# Adafruit_MAX31855_v2.net
KiCad netlist of a schematic drawn in EAGLE
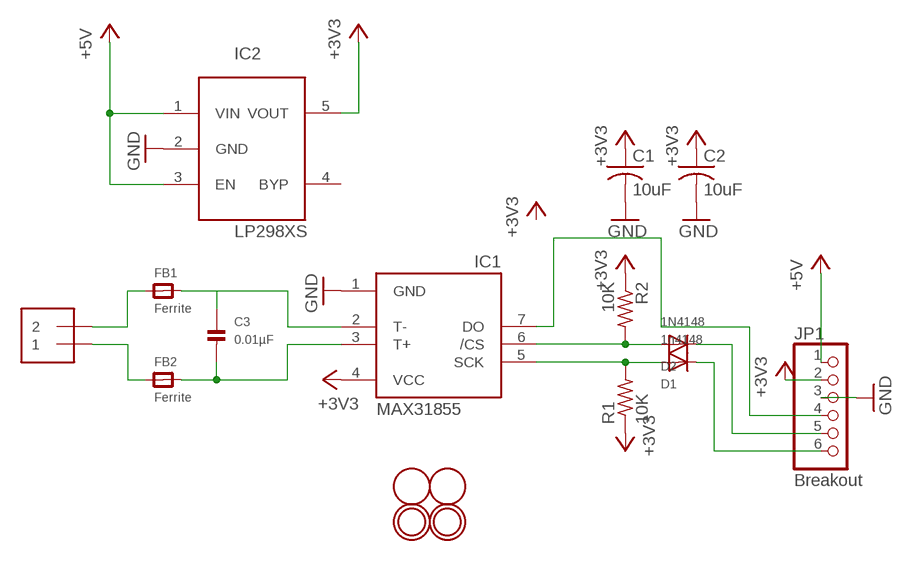
[diagram p0: schematic, sheet 1]

(export (version "E")
  (design (tool "Eeschema 10.0.6"))
  (components
    (comp (ref "C1")
      (value "10uF")
      (footprint "eagle-import:C0805K")
      (libsource (lib "eagle-import") (part "C-USC0805K"))
    )
    (comp (ref "C2")
      (value "10uF")
      (footprint "eagle-import:C0805K")
      (libsource (lib "eagle-import") (part "C-USC0805K"))
    )
    (comp (ref "C3")
      (value "0.01µF")
      (footprint "eagle-import:_0805")
      (libsource (lib "eagle-import") (part "CAP_CERAMIC_0805"))
    )
    (comp (ref "D1")
      (value "1n4148")
      (footprint "eagle-import:SOD-323F")
      (libsource (lib "eagle-import") (part "DIODESOD-323F"))
    )
    (comp (ref "D2")
      (value "1N4148")
      (footprint "eagle-import:SOD-323F")
      (libsource (lib "eagle-import") (part "DIODESOD-323F"))
    )
    (comp (ref "FB1")
      (value "Ferrite")
      (footprint "eagle-import:_0805")
      (libsource (lib "eagle-import") (part "FERRITE_0805"))
    )
    (comp (ref "FB2")
      (value "Ferrite")
      (footprint "eagle-import:_0805")
      (libsource (lib "eagle-import") (part "FERRITE_0805"))
    )
    (comp (ref "IC1")
      (value "MAX31855")
      (footprint "eagle-import:SO08")
      (libsource (lib "eagle-import") (part "MAX6675"))
    )
    (comp (ref "IC2")
      (value "LP298XS")
      (footprint "eagle-import:SOT23-5L")
      (libsource (lib "eagle-import") (part "LP298XS"))
    )
    (comp (ref "J1")
      (value "1X2-3.5MM")
      (footprint "eagle-import:1X2-3.5MM")
      (libsource (lib "eagle-import") (part "1X2-3.5MM"))
    )
    (comp (ref "JP1")
      (value "Breakout")
      (footprint "eagle-import:1X06_ROUND_76")
      (libsource (lib "eagle-import") (part "HEADER-1X676MIL"))
    )
    (comp (ref "R1")
      (value "10K")
      (footprint "eagle-import:R0805")
      (libsource (lib "eagle-import") (part "R-US_R0805"))
    )
    (comp (ref "R2")
      (value "10K")
      (footprint "eagle-import:R0805")
      (libsource (lib "eagle-import") (part "R-US_R0805"))
    )
    (comp (ref "U$1")
      (value "FIDUCIAL")
      (footprint "eagle-import:FIDUCIAL_1MM")
      (libsource (lib "eagle-import") (part "FIDUCIAL"))
    )
    (comp (ref "U$2")
      (value "FIDUCIAL")
      (footprint "eagle-import:FIDUCIAL_1MM")
      (libsource (lib "eagle-import") (part "FIDUCIAL"))
    )
    (comp (ref "U$4")
      (value "MOUNTINGHOLE2.0")
      (footprint "eagle-import:MOUNTINGHOLE_2.0_PLATED")
      (libsource (lib "eagle-import") (part "MOUNTINGHOLE2.0"))
    )
    (comp (ref "U$5")
      (value "MOUNTINGHOLE2.0")
      (footprint "eagle-import:MOUNTINGHOLE_2.0_PLATED")
      (libsource (lib "eagle-import") (part "MOUNTINGHOLE2.0"))
    )
  )
  (nets
    (net (code "1") (name "+3V3") (class "Default")
      (node (ref "C1") (pin "1") (pinfunction "1_1") (pintype "passive"))
      (node (ref "C2") (pin "1") (pinfunction "1_1") (pintype "passive"))
      (node (ref "IC1") (pin "4") (pinfunction "VCC_4") (pintype "power_in"))
      (node (ref "IC2") (pin "5") (pinfunction "VOUT_5") (pintype "bidirectional"))
      (node (ref "JP1") (pin "2") (pinfunction "2_2") (pintype "passive"))
      (node (ref "R1") (pin "1") (pinfunction "1_1") (pintype "passive"))
      (node (ref "R2") (pin "1") (pinfunction "1_1") (pintype "passive"))
    )
    (net (code "2") (name "+5V") (class "Default")
      (node (ref "IC2") (pin "1") (pinfunction "VIN_1") (pintype "bidirectional"))
      (node (ref "IC2") (pin "3") (pinfunction "EN_3") (pintype "bidirectional"))
      (node (ref "JP1") (pin "1") (pinfunction "1_1") (pintype "passive"))
    )
    (net (code "3") (name "GND") (class "Default")
      (node (ref "C1") (pin "2") (pinfunction "2_2") (pintype "passive"))
      (node (ref "C2") (pin "2") (pinfunction "2_2") (pintype "passive"))
      (node (ref "IC1") (pin "1") (pinfunction "GND_1") (pintype "power_in"))
      (node (ref "IC2") (pin "2") (pinfunction "GND_2") (pintype "bidirectional"))
      (node (ref "JP1") (pin "3") (pinfunction "3_3") (pintype "passive"))
    )
    (net (code "4") (name "Net-(C3-P$1)") (class "Default")
      (node (ref "C3") (pin "1") (pinfunction "P$1_1") (pintype "passive"))
      (node (ref "FB1") (pin "2") (pinfunction "P$2_2") (pintype "passive"))
      (node (ref "IC1") (pin "2") (pinfunction "T-_2") (pintype "input"))
    )
    (net (code "5") (name "Net-(C3-P$2)") (class "Default")
      (node (ref "C3") (pin "2") (pinfunction "P$2_2") (pintype "passive"))
      (node (ref "FB2") (pin "2") (pinfunction "P$2_2") (pintype "passive"))
      (node (ref "IC1") (pin "3") (pinfunction "T+_3") (pintype "input"))
    )
    (net (code "6") (name "Net-(D1-PadC)") (class "Default")
      (node (ref "D1") (pin "C") (pinfunction "C_C") (pintype "passive"))
      (node (ref "JP1") (pin "6") (pinfunction "6_6") (pintype "passive"))
    )
    (net (code "7") (name "Net-(D2-PadC)") (class "Default")
      (node (ref "D2") (pin "C") (pinfunction "C_C") (pintype "passive"))
      (node (ref "JP1") (pin "5") (pinfunction "5_5") (pintype "passive"))
    )
    (net (code "8") (name "Net-(FB1-P$1)") (class "Default")
      (node (ref "FB1") (pin "1") (pinfunction "P$1_1") (pintype "passive"))
      (node (ref "J1") (pin "2") (pinfunction "2_2") (pintype "passive"))
    )
    (net (code "9") (name "Net-(FB2-P$1)") (class "Default")
      (node (ref "FB2") (pin "1") (pinfunction "P$1_1") (pintype "passive"))
      (node (ref "J1") (pin "1") (pinfunction "1_1") (pintype "passive"))
    )
    (net (code "10") (name "Net-(IC1-DO)") (class "Default")
      (node (ref "IC1") (pin "7") (pinfunction "DO_7") (pintype "output"))
      (node (ref "JP1") (pin "4") (pinfunction "4_4") (pintype "passive"))
    )
    (net (code "11") (name "Net-(IC1-SCK)") (class "Default")
      (node (ref "D1") (pin "A") (pinfunction "A_A") (pintype "passive"))
      (node (ref "IC1") (pin "5") (pinfunction "SCK_5") (pintype "input"))
      (node (ref "R1") (pin "2") (pinfunction "2_2") (pintype "passive"))
    )
    (net (code "12") (name "Net-(IC1-{slash}CS)") (class "Default")
      (node (ref "D2") (pin "A") (pinfunction "A_A") (pintype "passive"))
      (node (ref "IC1") (pin "6") (pinfunction "/CS_6") (pintype "input"))
      (node (ref "R2") (pin "2") (pinfunction "2_2") (pintype "passive"))
    )
    (net (code "13") (name "unconnected-(IC2-BYP-Pad4)") (class "Default")
      (node (ref "IC2") (pin "4") (pinfunction "BYP_4") (pintype "bidirectional"))
    )
  )
)
